# score_anzeige_register.net
KiCad netlist of a schematic drawn in EAGLE
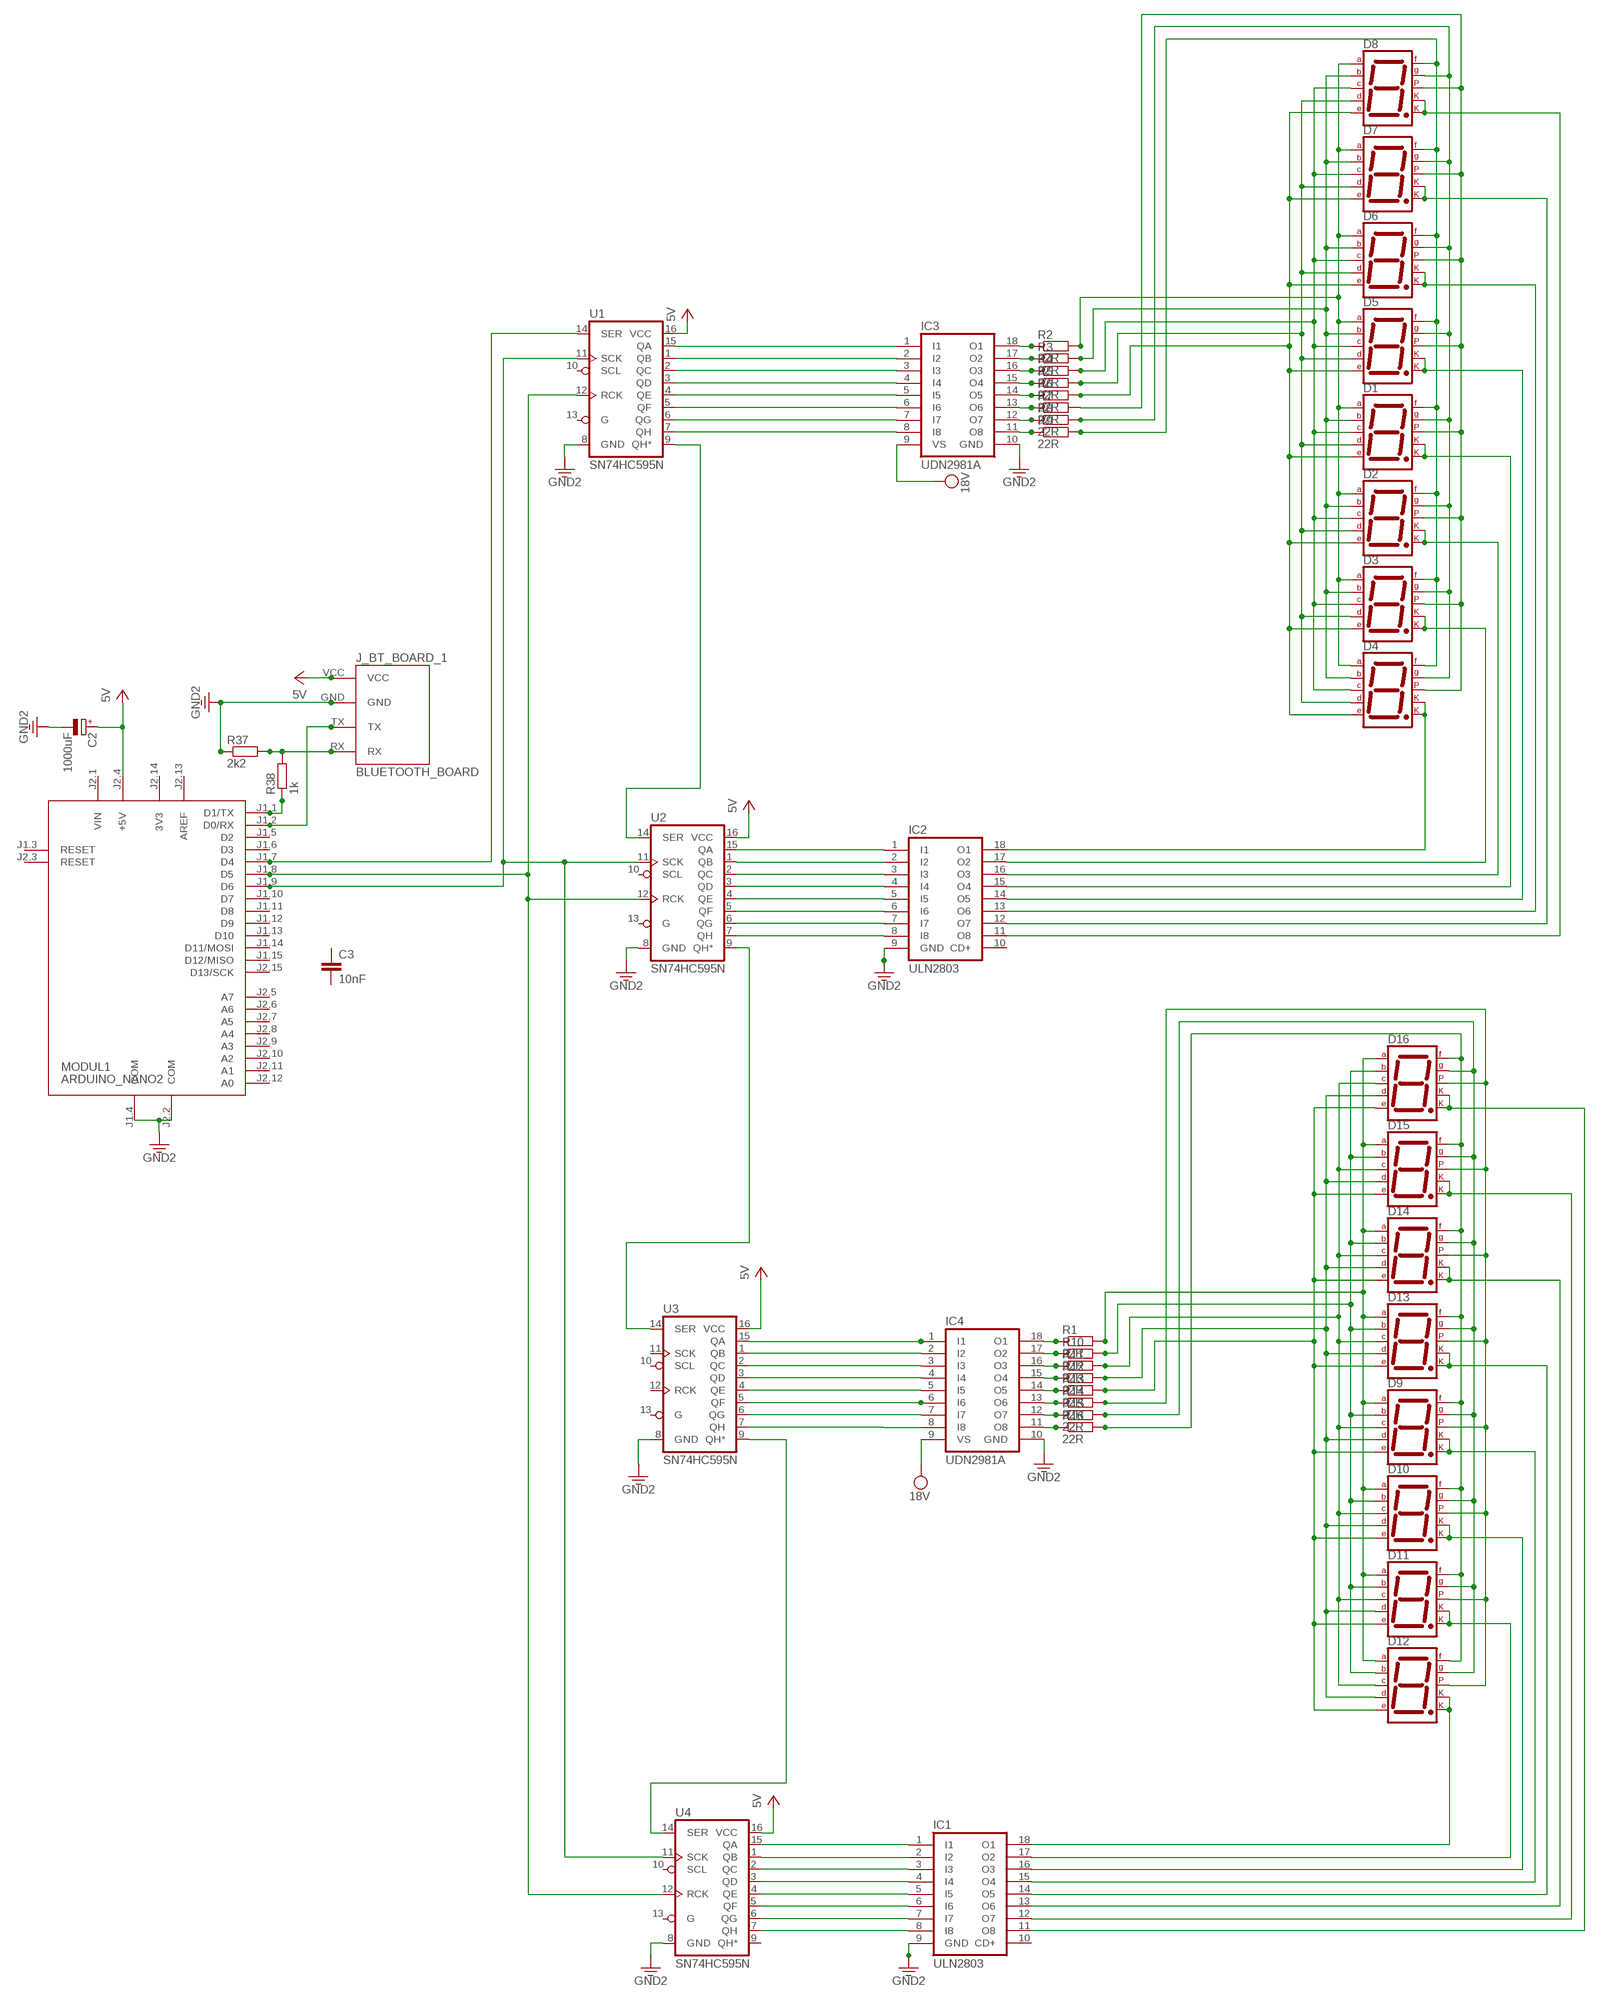
[diagram p0: schematic, sheet 1]

(export (version "E")
  (design (tool "Eeschema 10.0.6"))
  (components
    (comp (ref "C2")
      (value "1000uF")
      (footprint "eagle-import:E5-10,5")
      (libsource (lib "eagle-import") (part "CPOL-EUE5-10.5"))
    )
    (comp (ref "C3")
      (value "10nF")
      (footprint "eagle-import:C025-025X050")
      (libsource (lib "eagle-import") (part "C-EU025-025X050"))
    )
    (comp (ref "D1")
      (value "7SEG-MCK")
      (footprint "eagle-import:7SEG-7")
      (libsource (lib "eagle-import") (part "7SEG-MCK"))
    )
    (comp (ref "D2")
      (value "7SEG-MCK")
      (footprint "eagle-import:7SEG-7")
      (libsource (lib "eagle-import") (part "7SEG-MCK"))
    )
    (comp (ref "D3")
      (value "7SEG-MCK")
      (footprint "eagle-import:7SEG-7")
      (libsource (lib "eagle-import") (part "7SEG-MCK"))
    )
    (comp (ref "D4")
      (value "7SEG-MCK")
      (footprint "eagle-import:7SEG-7")
      (libsource (lib "eagle-import") (part "7SEG-MCK"))
    )
    (comp (ref "D5")
      (value "7SEG-MCK")
      (footprint "eagle-import:7SEG-7")
      (libsource (lib "eagle-import") (part "7SEG-MCK"))
    )
    (comp (ref "D6")
      (value "7SEG-MCK")
      (footprint "eagle-import:7SEG-7")
      (libsource (lib "eagle-import") (part "7SEG-MCK"))
    )
    (comp (ref "D7")
      (value "7SEG-MCK")
      (footprint "eagle-import:7SEG-7")
      (libsource (lib "eagle-import") (part "7SEG-MCK"))
    )
    (comp (ref "D8")
      (value "7SEG-MCK")
      (footprint "eagle-import:7SEG-7")
      (libsource (lib "eagle-import") (part "7SEG-MCK"))
    )
    (comp (ref "D9")
      (value "7SEG-MCK")
      (footprint "eagle-import:7SEG-7")
      (libsource (lib "eagle-import") (part "7SEG-MCK"))
    )
    (comp (ref "D10")
      (value "7SEG-MCK")
      (footprint "eagle-import:7SEG-7")
      (libsource (lib "eagle-import") (part "7SEG-MCK"))
    )
    (comp (ref "D11")
      (value "7SEG-MCK")
      (footprint "eagle-import:7SEG-7")
      (libsource (lib "eagle-import") (part "7SEG-MCK"))
    )
    (comp (ref "D12")
      (value "7SEG-MCK")
      (footprint "eagle-import:7SEG-7")
      (libsource (lib "eagle-import") (part "7SEG-MCK"))
    )
    (comp (ref "D13")
      (value "7SEG-MCK")
      (footprint "eagle-import:7SEG-7")
      (libsource (lib "eagle-import") (part "7SEG-MCK"))
    )
    (comp (ref "D14")
      (value "7SEG-MCK")
      (footprint "eagle-import:7SEG-7")
      (libsource (lib "eagle-import") (part "7SEG-MCK"))
    )
    (comp (ref "D15")
      (value "7SEG-MCK")
      (footprint "eagle-import:7SEG-7")
      (libsource (lib "eagle-import") (part "7SEG-MCK"))
    )
    (comp (ref "D16")
      (value "7SEG-MCK")
      (footprint "eagle-import:7SEG-7")
      (libsource (lib "eagle-import") (part "7SEG-MCK"))
    )
    (comp (ref "IC1")
      (value "ULN2803")
      (footprint "eagle-import:DIL18")
      (libsource (lib "eagle-import") (part "ULN2803A"))
    )
    (comp (ref "IC2")
      (value "ULN2803")
      (footprint "eagle-import:DIL18")
      (libsource (lib "eagle-import") (part "ULN2803A"))
    )
    (comp (ref "IC3")
      (value "UDN2981A")
      (footprint "eagle-import:DIL18")
      (libsource (lib "eagle-import") (part "UDN298A1"))
    )
    (comp (ref "IC4")
      (value "UDN2981A")
      (footprint "eagle-import:DIL18")
      (libsource (lib "eagle-import") (part "UDN298A1"))
    )
    (comp (ref "J_BT_BOARD_1")
      (value "BLUETOOTH_BOARD")
      (footprint "eagle-import:BT_BOARD_FOOTPRINT")
      (libsource (lib "eagle-import") (part "BLUETOOTH_BOARD"))
    )
    (comp (ref "MODUL1")
      (value "ARDUINO_NANO2")
      (footprint "eagle-import:ARDUINO_NANO2")
      (libsource (lib "eagle-import") (part "ARDUINO_NANO2"))
    )
    (comp (ref "R1")
      (value "22R")
      (footprint "eagle-import:0204_7")
      (libsource (lib "eagle-import") (part "R-EU_0204/7"))
    )
    (comp (ref "R2")
      (value "22R")
      (footprint "eagle-import:0204_7")
      (libsource (lib "eagle-import") (part "R-EU_0204/7"))
    )
    (comp (ref "R3")
      (value "22R")
      (footprint "eagle-import:0204_7")
      (libsource (lib "eagle-import") (part "R-EU_0204/7"))
    )
    (comp (ref "R4")
      (value "22R")
      (footprint "eagle-import:0204_7")
      (libsource (lib "eagle-import") (part "R-EU_0204/7"))
    )
    (comp (ref "R5")
      (value "22R")
      (footprint "eagle-import:0204_7")
      (libsource (lib "eagle-import") (part "R-EU_0204/7"))
    )
    (comp (ref "R6")
      (value "22R")
      (footprint "eagle-import:0204_7")
      (libsource (lib "eagle-import") (part "R-EU_0204/7"))
    )
    (comp (ref "R7")
      (value "22R")
      (footprint "eagle-import:0204_7")
      (libsource (lib "eagle-import") (part "R-EU_0204/7"))
    )
    (comp (ref "R8")
      (value "22R")
      (footprint "eagle-import:0204_7")
      (libsource (lib "eagle-import") (part "R-EU_0204/7"))
    )
    (comp (ref "R9")
      (value "22R")
      (footprint "eagle-import:0204_7")
      (libsource (lib "eagle-import") (part "R-EU_0204/7"))
    )
    (comp (ref "R10")
      (value "22R")
      (footprint "eagle-import:0204_7")
      (libsource (lib "eagle-import") (part "R-EU_0204/7"))
    )
    (comp (ref "R11")
      (value "22R")
      (footprint "eagle-import:0204_7")
      (libsource (lib "eagle-import") (part "R-EU_0204/7"))
    )
    (comp (ref "R12")
      (value "22R")
      (footprint "eagle-import:0204_7")
      (libsource (lib "eagle-import") (part "R-EU_0204/7"))
    )
    (comp (ref "R13")
      (value "22R")
      (footprint "eagle-import:0204_7")
      (libsource (lib "eagle-import") (part "R-EU_0204/7"))
    )
    (comp (ref "R14")
      (value "22R")
      (footprint "eagle-import:0204_7")
      (libsource (lib "eagle-import") (part "R-EU_0204/7"))
    )
    (comp (ref "R15")
      (value "22R")
      (footprint "eagle-import:0204_7")
      (libsource (lib "eagle-import") (part "R-EU_0204/7"))
    )
    (comp (ref "R16")
      (value "22R")
      (footprint "eagle-import:0204_7")
      (libsource (lib "eagle-import") (part "R-EU_0204/7"))
    )
    (comp (ref "R37")
      (value "2k2")
      (footprint "eagle-import:0204_7")
      (libsource (lib "eagle-import") (part "R-EU_0204/7"))
    )
    (comp (ref "R38")
      (value "1k")
      (footprint "eagle-import:0204_7")
      (libsource (lib "eagle-import") (part "R-EU_0204/7"))
    )
    (comp (ref "U1")
      (value "SN74HC595N")
      (footprint "eagle-import:DIP16")
      (libsource (lib "eagle-import") (part "74595NHC"))
    )
    (comp (ref "U2")
      (value "SN74HC595N")
      (footprint "eagle-import:DIP16")
      (libsource (lib "eagle-import") (part "74595NHC"))
    )
    (comp (ref "U3")
      (value "SN74HC595N")
      (footprint "eagle-import:DIP16")
      (libsource (lib "eagle-import") (part "74595NHC"))
    )
    (comp (ref "U4")
      (value "SN74HC595N")
      (footprint "eagle-import:DIP16")
      (libsource (lib "eagle-import") (part "74595NHC"))
    )
  )
  (nets
    (net (code "1") (name "/3V3") (class "Default")
      (node (ref "MODUL1") (pin "J2.14") (pinfunction "3V3_J2.14") (pintype "power_in"))
    )
    (net (code "2") (name "/AREF") (class "Default")
      (node (ref "MODUL1") (pin "J2.13") (pinfunction "AREF_J2.13") (pintype "power_in"))
    )
    (net (code "3") (name "/VIN") (class "Default")
      (node (ref "MODUL1") (pin "J2.1") (pinfunction "VIN_J2.1") (pintype "power_in"))
    )
    (net (code "4") (name "18V") (class "Default")
      (node (ref "C2") (pin "+") (pinfunction "+_+") (pintype "passive"))
      (node (ref "IC3") (pin "9") (pinfunction "VS_9") (pintype "passive"))
      (node (ref "IC4") (pin "9") (pinfunction "VS_9") (pintype "passive"))
      (node (ref "J_BT_BOARD_1") (pin "VCC") (pinfunction "VCC_VCC") (pintype "bidirectional"))
      (node (ref "MODUL1") (pin "J2.4") (pinfunction "+5V_J2.4") (pintype "power_in"))
      (node (ref "U1") (pin "16") (pinfunction "VCC_16") (pintype "power_in"))
      (node (ref "U2") (pin "16") (pinfunction "VCC_16") (pintype "power_in"))
      (node (ref "U3") (pin "16") (pinfunction "VCC_16") (pintype "power_in"))
      (node (ref "U4") (pin "16") (pinfunction "VCC_16") (pintype "power_in"))
    )
    (net (code "5") (name "GND2") (class "Default")
      (node (ref "C2") (pin "-") (pinfunction "-_-") (pintype "passive"))
      (node (ref "IC1") (pin "9") (pinfunction "GND_9") (pintype "power_in"))
      (node (ref "IC2") (pin "9") (pinfunction "GND_9") (pintype "power_in"))
      (node (ref "IC3") (pin "10") (pinfunction "GND_10") (pintype "power_in"))
      (node (ref "IC4") (pin "10") (pinfunction "GND_10") (pintype "power_in"))
      (node (ref "J_BT_BOARD_1") (pin "GND") (pinfunction "GND_GND") (pintype "bidirectional"))
      (node (ref "MODUL1") (pin "J1.4") (pinfunction "COM_J1.4") (pintype "power_in"))
      (node (ref "MODUL1") (pin "J2.2") (pinfunction "COM_J2.2") (pintype "power_in"))
      (node (ref "R37") (pin "1") (pinfunction "1_1") (pintype "passive"))
      (node (ref "U1") (pin "8") (pinfunction "GND_8") (pintype "power_in"))
      (node (ref "U2") (pin "8") (pinfunction "GND_8") (pintype "power_in"))
      (node (ref "U3") (pin "8") (pinfunction "GND_8") (pintype "power_in"))
      (node (ref "U4") (pin "8") (pinfunction "GND_8") (pintype "power_in"))
    )
    (net (code "6") (name "Net-(D1-A)") (class "Default")
      (node (ref "D1") (pin "10") (pinfunction "A_10") (pintype "passive"))
      (node (ref "D2") (pin "10") (pinfunction "A_10") (pintype "passive"))
      (node (ref "D3") (pin "10") (pinfunction "A_10") (pintype "passive"))
      (node (ref "D4") (pin "10") (pinfunction "A_10") (pintype "passive"))
      (node (ref "D5") (pin "10") (pinfunction "A_10") (pintype "passive"))
      (node (ref "D6") (pin "10") (pinfunction "A_10") (pintype "passive"))
      (node (ref "D7") (pin "10") (pinfunction "A_10") (pintype "passive"))
      (node (ref "D8") (pin "10") (pinfunction "A_10") (pintype "passive"))
      (node (ref "R2") (pin "2") (pinfunction "2_2") (pintype "passive"))
    )
    (net (code "7") (name "Net-(D1-B)") (class "Default")
      (node (ref "D1") (pin "9") (pinfunction "B_9") (pintype "passive"))
      (node (ref "D2") (pin "9") (pinfunction "B_9") (pintype "passive"))
      (node (ref "D3") (pin "9") (pinfunction "B_9") (pintype "passive"))
      (node (ref "D4") (pin "9") (pinfunction "B_9") (pintype "passive"))
      (node (ref "D5") (pin "9") (pinfunction "B_9") (pintype "passive"))
      (node (ref "D6") (pin "9") (pinfunction "B_9") (pintype "passive"))
      (node (ref "D7") (pin "9") (pinfunction "B_9") (pintype "passive"))
      (node (ref "D8") (pin "9") (pinfunction "B_9") (pintype "passive"))
      (node (ref "R3") (pin "2") (pinfunction "2_2") (pintype "passive"))
    )
    (net (code "8") (name "Net-(D1-C)") (class "Default")
      (node (ref "D1") (pin "8") (pinfunction "C_8") (pintype "passive"))
      (node (ref "D2") (pin "8") (pinfunction "C_8") (pintype "passive"))
      (node (ref "D3") (pin "8") (pinfunction "C_8") (pintype "passive"))
      (node (ref "D4") (pin "8") (pinfunction "C_8") (pintype "passive"))
      (node (ref "D5") (pin "8") (pinfunction "C_8") (pintype "passive"))
      (node (ref "D6") (pin "8") (pinfunction "C_8") (pintype "passive"))
      (node (ref "D7") (pin "8") (pinfunction "C_8") (pintype "passive"))
      (node (ref "D8") (pin "8") (pinfunction "C_8") (pintype "passive"))
      (node (ref "R4") (pin "2") (pinfunction "2_2") (pintype "passive"))
    )
    (net (code "9") (name "Net-(D1-CK1)") (class "Default")
      (node (ref "D1") (pin "1") (pinfunction "CK1_1") (pintype "passive"))
      (node (ref "D1") (pin "6") (pinfunction "CK2_6") (pintype "passive"))
      (node (ref "IC2") (pin "15") (pinfunction "O4_15") (pintype "open_collector"))
    )
    (net (code "10") (name "Net-(D1-D)") (class "Default")
      (node (ref "D1") (pin "5") (pinfunction "D_5") (pintype "passive"))
      (node (ref "D2") (pin "5") (pinfunction "D_5") (pintype "passive"))
      (node (ref "D3") (pin "5") (pinfunction "D_5") (pintype "passive"))
      (node (ref "D4") (pin "5") (pinfunction "D_5") (pintype "passive"))
      (node (ref "D5") (pin "5") (pinfunction "D_5") (pintype "passive"))
      (node (ref "D6") (pin "5") (pinfunction "D_5") (pintype "passive"))
      (node (ref "D7") (pin "5") (pinfunction "D_5") (pintype "passive"))
      (node (ref "D8") (pin "5") (pinfunction "D_5") (pintype "passive"))
      (node (ref "R5") (pin "2") (pinfunction "2_2") (pintype "passive"))
    )
    (net (code "11") (name "Net-(D1-DP)") (class "Default")
      (node (ref "D1") (pin "7") (pinfunction "DP_7") (pintype "passive"))
      (node (ref "D2") (pin "7") (pinfunction "DP_7") (pintype "passive"))
      (node (ref "D3") (pin "7") (pinfunction "DP_7") (pintype "passive"))
      (node (ref "D4") (pin "7") (pinfunction "DP_7") (pintype "passive"))
      (node (ref "D5") (pin "7") (pinfunction "DP_7") (pintype "passive"))
      (node (ref "D6") (pin "7") (pinfunction "DP_7") (pintype "passive"))
      (node (ref "D7") (pin "7") (pinfunction "DP_7") (pintype "passive"))
      (node (ref "D8") (pin "7") (pinfunction "DP_7") (pintype "passive"))
      (node (ref "R7") (pin "2") (pinfunction "2_2") (pintype "passive"))
    )
    (net (code "12") (name "Net-(D1-E)") (class "Default")
      (node (ref "D1") (pin "4") (pinfunction "E_4") (pintype "passive"))
      (node (ref "D2") (pin "4") (pinfunction "E_4") (pintype "passive"))
      (node (ref "D3") (pin "4") (pinfunction "E_4") (pintype "passive"))
      (node (ref "D4") (pin "4") (pinfunction "E_4") (pintype "passive"))
      (node (ref "D5") (pin "4") (pinfunction "E_4") (pintype "passive"))
      (node (ref "D6") (pin "4") (pinfunction "E_4") (pintype "passive"))
      (node (ref "D7") (pin "4") (pinfunction "E_4") (pintype "passive"))
      (node (ref "D8") (pin "4") (pinfunction "E_4") (pintype "passive"))
      (node (ref "R6") (pin "2") (pinfunction "2_2") (pintype "passive"))
    )
    (net (code "13") (name "Net-(D1-F)") (class "Default")
      (node (ref "D1") (pin "2") (pinfunction "F_2") (pintype "passive"))
      (node (ref "D2") (pin "2") (pinfunction "F_2") (pintype "passive"))
      (node (ref "D3") (pin "2") (pinfunction "F_2") (pintype "passive"))
      (node (ref "D4") (pin "2") (pinfunction "F_2") (pintype "passive"))
      (node (ref "D5") (pin "2") (pinfunction "F_2") (pintype "passive"))
      (node (ref "D6") (pin "2") (pinfunction "F_2") (pintype "passive"))
      (node (ref "D7") (pin "2") (pinfunction "F_2") (pintype "passive"))
      (node (ref "D8") (pin "2") (pinfunction "F_2") (pintype "passive"))
      (node (ref "R9") (pin "2") (pinfunction "2_2") (pintype "passive"))
    )
    (net (code "14") (name "Net-(D1-G)") (class "Default")
      (node (ref "D1") (pin "3") (pinfunction "G_3") (pintype "passive"))
      (node (ref "D2") (pin "3") (pinfunction "G_3") (pintype "passive"))
      (node (ref "D3") (pin "3") (pinfunction "G_3") (pintype "passive"))
      (node (ref "D4") (pin "3") (pinfunction "G_3") (pintype "passive"))
      (node (ref "D5") (pin "3") (pinfunction "G_3") (pintype "passive"))
      (node (ref "D6") (pin "3") (pinfunction "G_3") (pintype "passive"))
      (node (ref "D7") (pin "3") (pinfunction "G_3") (pintype "passive"))
      (node (ref "D8") (pin "3") (pinfunction "G_3") (pintype "passive"))
      (node (ref "R8") (pin "2") (pinfunction "2_2") (pintype "passive"))
    )
    (net (code "15") (name "Net-(D2-CK1)") (class "Default")
      (node (ref "D2") (pin "1") (pinfunction "CK1_1") (pintype "passive"))
      (node (ref "D2") (pin "6") (pinfunction "CK2_6") (pintype "passive"))
      (node (ref "IC2") (pin "16") (pinfunction "O3_16") (pintype "open_collector"))
    )
    (net (code "16") (name "Net-(D3-CK1)") (class "Default")
      (node (ref "D3") (pin "1") (pinfunction "CK1_1") (pintype "passive"))
      (node (ref "D3") (pin "6") (pinfunction "CK2_6") (pintype "passive"))
      (node (ref "IC2") (pin "17") (pinfunction "O2_17") (pintype "open_collector"))
    )
    (net (code "17") (name "Net-(D4-CK1)") (class "Default")
      (node (ref "D4") (pin "1") (pinfunction "CK1_1") (pintype "passive"))
      (node (ref "D4") (pin "6") (pinfunction "CK2_6") (pintype "passive"))
      (node (ref "IC2") (pin "18") (pinfunction "O1_18") (pintype "open_collector"))
    )
    (net (code "18") (name "Net-(D5-CK1)") (class "Default")
      (node (ref "D5") (pin "1") (pinfunction "CK1_1") (pintype "passive"))
      (node (ref "D5") (pin "6") (pinfunction "CK2_6") (pintype "passive"))
      (node (ref "IC2") (pin "14") (pinfunction "O5_14") (pintype "open_collector"))
    )
    (net (code "19") (name "Net-(D6-CK1)") (class "Default")
      (node (ref "D6") (pin "1") (pinfunction "CK1_1") (pintype "passive"))
      (node (ref "D6") (pin "6") (pinfunction "CK2_6") (pintype "passive"))
      (node (ref "IC2") (pin "13") (pinfunction "O6_13") (pintype "open_collector"))
    )
    (net (code "20") (name "Net-(D7-CK1)") (class "Default")
      (node (ref "D7") (pin "1") (pinfunction "CK1_1") (pintype "passive"))
      (node (ref "D7") (pin "6") (pinfunction "CK2_6") (pintype "passive"))
      (node (ref "IC2") (pin "12") (pinfunction "O7_12") (pintype "open_collector"))
    )
    (net (code "21") (name "Net-(D8-CK1)") (class "Default")
      (node (ref "D8") (pin "1") (pinfunction "CK1_1") (pintype "passive"))
      (node (ref "D8") (pin "6") (pinfunction "CK2_6") (pintype "passive"))
      (node (ref "IC2") (pin "11") (pinfunction "O8_11") (pintype "open_collector"))
    )
    (net (code "22") (name "Net-(D9-CK1)") (class "Default")
      (node (ref "D9") (pin "1") (pinfunction "CK1_1") (pintype "passive"))
      (node (ref "D9") (pin "6") (pinfunction "CK2_6") (pintype "passive"))
      (node (ref "IC1") (pin "15") (pinfunction "O4_15") (pintype "open_collector"))
    )
    (net (code "23") (name "Net-(D10-A)") (class "Default")
      (node (ref "D10") (pin "10") (pinfunction "A_10") (pintype "passive"))
      (node (ref "D11") (pin "10") (pinfunction "A_10") (pintype "passive"))
      (node (ref "D12") (pin "10") (pinfunction "A_10") (pintype "passive"))
      (node (ref "D13") (pin "10") (pinfunction "A_10") (pintype "passive"))
      (node (ref "D14") (pin "10") (pinfunction "A_10") (pintype "passive"))
      (node (ref "D15") (pin "10") (pinfunction "A_10") (pintype "passive"))
      (node (ref "D16") (pin "10") (pinfunction "A_10") (pintype "passive"))
      (node (ref "D9") (pin "10") (pinfunction "A_10") (pintype "passive"))
      (node (ref "R1") (pin "2") (pinfunction "2_2") (pintype "passive"))
    )
    (net (code "24") (name "Net-(D10-B)") (class "Default")
      (node (ref "D10") (pin "9") (pinfunction "B_9") (pintype "passive"))
      (node (ref "D11") (pin "9") (pinfunction "B_9") (pintype "passive"))
      (node (ref "D12") (pin "9") (pinfunction "B_9") (pintype "passive"))
      (node (ref "D13") (pin "9") (pinfunction "B_9") (pintype "passive"))
      (node (ref "D14") (pin "9") (pinfunction "B_9") (pintype "passive"))
      (node (ref "D15") (pin "9") (pinfunction "B_9") (pintype "passive"))
      (node (ref "D16") (pin "9") (pinfunction "B_9") (pintype "passive"))
      (node (ref "D9") (pin "9") (pinfunction "B_9") (pintype "passive"))
      (node (ref "R10") (pin "2") (pinfunction "2_2") (pintype "passive"))
    )
    (net (code "25") (name "Net-(D10-C)") (class "Default")
      (node (ref "D10") (pin "8") (pinfunction "C_8") (pintype "passive"))
      (node (ref "D11") (pin "8") (pinfunction "C_8") (pintype "passive"))
      (node (ref "D12") (pin "8") (pinfunction "C_8") (pintype "passive"))
      (node (ref "D13") (pin "8") (pinfunction "C_8") (pintype "passive"))
      (node (ref "D14") (pin "8") (pinfunction "C_8") (pintype "passive"))
      (node (ref "D15") (pin "8") (pinfunction "C_8") (pintype "passive"))
      (node (ref "D16") (pin "8") (pinfunction "C_8") (pintype "passive"))
      (node (ref "D9") (pin "8") (pinfunction "C_8") (pintype "passive"))
      (node (ref "R11") (pin "2") (pinfunction "2_2") (pintype "passive"))
    )
    (net (code "26") (name "Net-(D10-CK1)") (class "Default")
      (node (ref "D10") (pin "1") (pinfunction "CK1_1") (pintype "passive"))
      (node (ref "D10") (pin "6") (pinfunction "CK2_6") (pintype "passive"))
      (node (ref "IC1") (pin "16") (pinfunction "O3_16") (pintype "open_collector"))
    )
    (net (code "27") (name "Net-(D10-D)") (class "Default")
      (node (ref "D10") (pin "5") (pinfunction "D_5") (pintype "passive"))
      (node (ref "D11") (pin "5") (pinfunction "D_5") (pintype "passive"))
      (node (ref "D12") (pin "5") (pinfunction "D_5") (pintype "passive"))
      (node (ref "D13") (pin "5") (pinfunction "D_5") (pintype "passive"))
      (node (ref "D14") (pin "5") (pinfunction "D_5") (pintype "passive"))
      (node (ref "D15") (pin "5") (pinfunction "D_5") (pintype "passive"))
      (node (ref "D16") (pin "5") (pinfunction "D_5") (pintype "passive"))
      (node (ref "D9") (pin "5") (pinfunction "D_5") (pintype "passive"))
      (node (ref "R12") (pin "2") (pinfunction "2_2") (pintype "passive"))
    )
    (net (code "28") (name "Net-(D10-DP)") (class "Default")
      (node (ref "D10") (pin "7") (pinfunction "DP_7") (pintype "passive"))
      (node (ref "D11") (pin "7") (pinfunction "DP_7") (pintype "passive"))
      (node (ref "D12") (pin "7") (pinfunction "DP_7") (pintype "passive"))
      (node (ref "D13") (pin "7") (pinfunction "DP_7") (pintype "passive"))
      (node (ref "D14") (pin "7") (pinfunction "DP_7") (pintype "passive"))
      (node (ref "D15") (pin "7") (pinfunction "DP_7") (pintype "passive"))
      (node (ref "D16") (pin "7") (pinfunction "DP_7") (pintype "passive"))
      (node (ref "D9") (pin "7") (pinfunction "DP_7") (pintype "passive"))
      (node (ref "R14") (pin "2") (pinfunction "2_2") (pintype "passive"))
    )
    (net (code "29") (name "Net-(D10-E)") (class "Default")
      (node (ref "D10") (pin "4") (pinfunction "E_4") (pintype "passive"))
      (node (ref "D11") (pin "4") (pinfunction "E_4") (pintype "passive"))
      (node (ref "D12") (pin "4") (pinfunction "E_4") (pintype "passive"))
      (node (ref "D13") (pin "4") (pinfunction "E_4") (pintype "passive"))
      (node (ref "D14") (pin "4") (pinfunction "E_4") (pintype "passive"))
      (node (ref "D15") (pin "4") (pinfunction "E_4") (pintype "passive"))
      (node (ref "D16") (pin "4") (pinfunction "E_4") (pintype "passive"))
      (node (ref "D9") (pin "4") (pinfunction "E_4") (pintype "passive"))
      (node (ref "R13") (pin "2") (pinfunction "2_2") (pintype "passive"))
    )
    (net (code "30") (name "Net-(D10-F)") (class "Default")
      (node (ref "D10") (pin "2") (pinfunction "F_2") (pintype "passive"))
      (node (ref "D11") (pin "2") (pinfunction "F_2") (pintype "passive"))
      (node (ref "D12") (pin "2") (pinfunction "F_2") (pintype "passive"))
      (node (ref "D13") (pin "2") (pinfunction "F_2") (pintype "passive"))
      (node (ref "D14") (pin "2") (pinfunction "F_2") (pintype "passive"))
      (node (ref "D15") (pin "2") (pinfunction "F_2") (pintype "passive"))
      (node (ref "D16") (pin "2") (pinfunction "F_2") (pintype "passive"))
      (node (ref "D9") (pin "2") (pinfunction "F_2") (pintype "passive"))
      (node (ref "R16") (pin "2") (pinfunction "2_2") (pintype "passive"))
    )
    (net (code "31") (name "Net-(D10-G)") (class "Default")
      (node (ref "D10") (pin "3") (pinfunction "G_3") (pintype "passive"))
      (node (ref "D11") (pin "3") (pinfunction "G_3") (pintype "passive"))
      (node (ref "D12") (pin "3") (pinfunction "G_3") (pintype "passive"))
      (node (ref "D13") (pin "3") (pinfunction "G_3") (pintype "passive"))
      (node (ref "D14") (pin "3") (pinfunction "G_3") (pintype "passive"))
      (node (ref "D15") (pin "3") (pinfunction "G_3") (pintype "passive"))
      (node (ref "D16") (pin "3") (pinfunction "G_3") (pintype "passive"))
      (node (ref "D9") (pin "3") (pinfunction "G_3") (pintype "passive"))
      (node (ref "R15") (pin "2") (pinfunction "2_2") (pintype "passive"))
    )
    (net (code "32") (name "Net-(D11-CK1)") (class "Default")
      (node (ref "D11") (pin "1") (pinfunction "CK1_1") (pintype "passive"))
      (node (ref "D11") (pin "6") (pinfunction "CK2_6") (pintype "passive"))
      (node (ref "IC1") (pin "17") (pinfunction "O2_17") (pintype "open_collector"))
    )
    (net (code "33") (name "Net-(D12-CK1)") (class "Default")
      (node (ref "D12") (pin "1") (pinfunction "CK1_1") (pintype "passive"))
      (node (ref "D12") (pin "6") (pinfunction "CK2_6") (pintype "passive"))
      (node (ref "IC1") (pin "18") (pinfunction "O1_18") (pintype "open_collector"))
    )
    (net (code "34") (name "Net-(D13-CK1)") (class "Default")
      (node (ref "D13") (pin "1") (pinfunction "CK1_1") (pintype "passive"))
      (node (ref "D13") (pin "6") (pinfunction "CK2_6") (pintype "passive"))
      (node (ref "IC1") (pin "14") (pinfunction "O5_14") (pintype "open_collector"))
    )
    (net (code "35") (name "Net-(D14-CK1)") (class "Default")
      (node (ref "D14") (pin "1") (pinfunction "CK1_1") (pintype "passive"))
      (node (ref "D14") (pin "6") (pinfunction "CK2_6") (pintype "passive"))
      (node (ref "IC1") (pin "13") (pinfunction "O6_13") (pintype "open_collector"))
    )
    (net (code "36") (name "Net-(D15-CK1)") (class "Default")
      (node (ref "D15") (pin "1") (pinfunction "CK1_1") (pintype "passive"))
      (node (ref "D15") (pin "6") (pinfunction "CK2_6") (pintype "passive"))
      (node (ref "IC1") (pin "12") (pinfunction "O7_12") (pintype "open_collector"))
    )
    (net (code "37") (name "Net-(D16-CK1)") (class "Default")
      (node (ref "D16") (pin "1") (pinfunction "CK1_1") (pintype "passive"))
      (node (ref "D16") (pin "6") (pinfunction "CK2_6") (pintype "passive"))
      (node (ref "IC1") (pin "11") (pinfunction "O8_11") (pintype "open_collector"))
    )
    (net (code "38") (name "Net-(IC1-I1)") (class "Default")
      (node (ref "IC1") (pin "1") (pinfunction "I1_1") (pintype "input"))
      (node (ref "U4") (pin "15") (pinfunction "QA_15") (pintype "tri_state"))
    )
    (net (code "39") (name "Net-(IC1-I2)") (class "Default")
      (node (ref "IC1") (pin "2") (pinfunction "I2_2") (pintype "input"))
      (node (ref "U4") (pin "1") (pinfunction "QB_1") (pintype "tri_state"))
    )
    (net (code "40") (name "Net-(IC1-I3)") (class "Default")
      (node (ref "IC1") (pin "3") (pinfunction "I3_3") (pintype "input"))
      (node (ref "U4") (pin "2") (pinfunction "QC_2") (pintype "tri_state"))
    )
    (net (code "41") (name "Net-(IC1-I4)") (class "Default")
      (node (ref "IC1") (pin "4") (pinfunction "I4_4") (pintype "input"))
      (node (ref "U4") (pin "3") (pinfunction "QD_3") (pintype "tri_state"))
    )
    (net (code "42") (name "Net-(IC1-I5)") (class "Default")
      (node (ref "IC1") (pin "5") (pinfunction "I5_5") (pintype "input"))
      (node (ref "U4") (pin "4") (pinfunction "QE_4") (pintype "tri_state"))
    )
    (net (code "43") (name "Net-(IC1-I6)") (class "Default")
      (node (ref "IC1") (pin "6") (pinfunction "I6_6") (pintype "input"))
      (node (ref "U4") (pin "5") (pinfunction "QF_5") (pintype "tri_state"))
    )
    (net (code "44") (name "Net-(IC1-I7)") (class "Default")
      (node (ref "IC1") (pin "7") (pinfunction "I7_7") (pintype "input"))
      (node (ref "U4") (pin "6") (pinfunction "QG_6") (pintype "tri_state"))
    )
    (net (code "45") (name "Net-(IC1-I8)") (class "Default")
      (node (ref "IC1") (pin "8") (pinfunction "I8_8") (pintype "input"))
      (node (ref "U4") (pin "7") (pinfunction "QH_7") (pintype "tri_state"))
    )
    (net (code "46") (name "Net-(IC2-I1)") (class "Default")
      (node (ref "IC2") (pin "1") (pinfunction "I1_1") (pintype "input"))
      (node (ref "U2") (pin "15") (pinfunction "QA_15") (pintype "tri_state"))
    )
    (net (code "47") (name "Net-(IC2-I2)") (class "Default")
      (node (ref "IC2") (pin "2") (pinfunction "I2_2") (pintype "input"))
      (node (ref "U2") (pin "1") (pinfunction "QB_1") (pintype "tri_state"))
    )
    (net (code "48") (name "Net-(IC2-I3)") (class "Default")
      (node (ref "IC2") (pin "3") (pinfunction "I3_3") (pintype "input"))
      (node (ref "U2") (pin "2") (pinfunction "QC_2") (pintype "tri_state"))
    )
    (net (code "49") (name "Net-(IC2-I4)") (class "Default")
      (node (ref "IC2") (pin "4") (pinfunction "I4_4") (pintype "input"))
      (node (ref "U2") (pin "3") (pinfunction "QD_3") (pintype "tri_state"))
    )
    (net (code "50") (name "Net-(IC2-I5)") (class "Default")
      (node (ref "IC2") (pin "5") (pinfunction "I5_5") (pintype "input"))
      (node (ref "U2") (pin "4") (pinfunction "QE_4") (pintype "tri_state"))
    )
    (net (code "51") (name "Net-(IC2-I6)") (class "Default")
      (node (ref "IC2") (pin "6") (pinfunction "I6_6") (pintype "input"))
      (node (ref "U2") (pin "5") (pinfunction "QF_5") (pintype "tri_state"))
    )
    (net (code "52") (name "Net-(IC2-I7)") (class "Default")
      (node (ref "IC2") (pin "7") (pinfunction "I7_7") (pintype "input"))
      (node (ref "U2") (pin "6") (pinfunction "QG_6") (pintype "tri_state"))
    )
    (net (code "53") (name "Net-(IC2-I8)") (class "Default")
      (node (ref "IC2") (pin "8") (pinfunction "I8_8") (pintype "input"))
      (node (ref "U2") (pin "7") (pinfunction "QH_7") (pintype "tri_state"))
    )
    (net (code "54") (name "Net-(IC3-I1)") (class "Default")
      (node (ref "IC3") (pin "1") (pinfunction "I1_1") (pintype "input"))
      (node (ref "U1") (pin "15") (pinfunction "QA_15") (pintype "tri_state"))
    )
    (net (code "55") (name "Net-(IC3-I2)") (class "Default")
      (node (ref "IC3") (pin "2") (pinfunction "I2_2") (pintype "input"))
      (node (ref "U1") (pin "1") (pinfunction "QB_1") (pintype "tri_state"))
    )
    (net (code "56") (name "Net-(IC3-I3)") (class "Default")
      (node (ref "IC3") (pin "3") (pinfunction "I3_3") (pintype "input"))
      (node (ref "U1") (pin "2") (pinfunction "QC_2") (pintype "tri_state"))
    )
    (net (code "57") (name "Net-(IC3-I4)") (class "Default")
      (node (ref "IC3") (pin "4") (pinfunction "I4_4") (pintype "input"))
      (node (ref "U1") (pin "3") (pinfunction "QD_3") (pintype "tri_state"))
    )
    (net (code "58") (name "Net-(IC3-I5)") (class "Default")
      (node (ref "IC3") (pin "5") (pinfunction "I5_5") (pintype "input"))
      (node (ref "U1") (pin "4") (pinfunction "QE_4") (pintype "tri_state"))
    )
    (net (code "59") (name "Net-(IC3-I6)") (class "Default")
      (node (ref "IC3") (pin "6") (pinfunction "I6_6") (pintype "input"))
      (node (ref "U1") (pin "5") (pinfunction "QF_5") (pintype "tri_state"))
    )
    (net (code "60") (name "Net-(IC3-I7)") (class "Default")
      (node (ref "IC3") (pin "7") (pinfunction "I7_7") (pintype "input"))
      (node (ref "U1") (pin "6") (pinfunction "QG_6") (pintype "tri_state"))
    )
    (net (code "61") (name "Net-(IC3-I8)") (class "Default")
      (node (ref "IC3") (pin "8") (pinfunction "I8_8") (pintype "input"))
      (node (ref "U1") (pin "7") (pinfunction "QH_7") (pintype "tri_state"))
    )
    (net (code "62") (name "Net-(IC3-O1)") (class "Default")
      (node (ref "IC3") (pin "18") (pinfunction "O1_18") (pintype "open_collector"))
      (node (ref "R2") (pin "1") (pinfunction "1_1") (pintype "passive"))
    )
    (net (code "63") (name "Net-(IC3-O2)") (class "Default")
      (node (ref "IC3") (pin "17") (pinfunction "O2_17") (pintype "open_collector"))
      (node (ref "R3") (pin "1") (pinfunction "1_1") (pintype "passive"))
    )
    (net (code "64") (name "Net-(IC3-O3)") (class "Default")
      (node (ref "IC3") (pin "16") (pinfunction "O3_16") (pintype "open_collector"))
      (node (ref "R4") (pin "1") (pinfunction "1_1") (pintype "passive"))
    )
    (net (code "65") (name "Net-(IC3-O4)") (class "Default")
      (node (ref "IC3") (pin "15") (pinfunction "O4_15") (pintype "open_collector"))
      (node (ref "R5") (pin "1") (pinfunction "1_1") (pintype "passive"))
    )
    (net (code "66") (name "Net-(IC3-O5)") (class "Default")
      (node (ref "IC3") (pin "14") (pinfunction "O5_14") (pintype "open_collector"))
      (node (ref "R6") (pin "1") (pinfunction "1_1") (pintype "passive"))
    )
    (net (code "67") (name "Net-(IC3-O6)") (class "Default")
      (node (ref "IC3") (pin "13") (pinfunction "O6_13") (pintype "open_collector"))
      (node (ref "R7") (pin "1") (pinfunction "1_1") (pintype "passive"))
    )
    (net (code "68") (name "Net-(IC3-O7)") (class "Default")
      (node (ref "IC3") (pin "12") (pinfunction "O7_12") (pintype "open_collector"))
      (node (ref "R8") (pin "1") (pinfunction "1_1") (pintype "passive"))
    )
    (net (code "69") (name "Net-(IC3-O8)") (class "Default")
      (node (ref "IC3") (pin "11") (pinfunction "O8_11") (pintype "open_collector"))
      (node (ref "R9") (pin "1") (pinfunction "1_1") (pintype "passive"))
    )
    (net (code "70") (name "Net-(IC4-I1)") (class "Default")
      (node (ref "IC4") (pin "1") (pinfunction "I1_1") (pintype "input"))
      (node (ref "U3") (pin "15") (pinfunction "QA_15") (pintype "tri_state"))
    )
    (net (code "71") (name "Net-(IC4-I2)") (class "Default")
      (node (ref "IC4") (pin "2") (pinfunction "I2_2") (pintype "input"))
      (node (ref "U3") (pin "1") (pinfunction "QB_1") (pintype "tri_state"))
    )
    (net (code "72") (name "Net-(IC4-I3)") (class "Default")
      (node (ref "IC4") (pin "3") (pinfunction "I3_3") (pintype "input"))
      (node (ref "U3") (pin "2") (pinfunction "QC_2") (pintype "tri_state"))
    )
    (net (code "73") (name "Net-(IC4-I4)") (class "Default")
      (node (ref "IC4") (pin "4") (pinfunction "I4_4") (pintype "input"))
      (node (ref "U3") (pin "3") (pinfunction "QD_3") (pintype "tri_state"))
    )
    (net (code "74") (name "Net-(IC4-I5)") (class "Default")
      (node (ref "IC4") (pin "5") (pinfunction "I5_5") (pintype "input"))
      (node (ref "U3") (pin "4") (pinfunction "QE_4") (pintype "tri_state"))
    )
    (net (code "75") (name "Net-(IC4-I6)") (class "Default")
      (node (ref "IC4") (pin "6") (pinfunction "I6_6") (pintype "input"))
      (node (ref "U3") (pin "5") (pinfunction "QF_5") (pintype "tri_state"))
    )
    (net (code "76") (name "Net-(IC4-I7)") (class "Default")
      (node (ref "IC4") (pin "7") (pinfunction "I7_7") (pintype "input"))
      (node (ref "U3") (pin "6") (pinfunction "QG_6") (pintype "tri_state"))
    )
    (net (code "77") (name "Net-(IC4-I8)") (class "Default")
      (node (ref "IC4") (pin "8") (pinfunction "I8_8") (pintype "input"))
      (node (ref "U3") (pin "7") (pinfunction "QH_7") (pintype "tri_state"))
    )
    (net (code "78") (name "Net-(IC4-O1)") (class "Default")
      (node (ref "IC4") (pin "18") (pinfunction "O1_18") (pintype "open_collector"))
      (node (ref "R1") (pin "1") (pinfunction "1_1") (pintype "passive"))
    )
    (net (code "79") (name "Net-(IC4-O2)") (class "Default")
      (node (ref "IC4") (pin "17") (pinfunction "O2_17") (pintype "open_collector"))
      (node (ref "R10") (pin "1") (pinfunction "1_1") (pintype "passive"))
    )
    (net (code "80") (name "Net-(IC4-O3)") (class "Default")
      (node (ref "IC4") (pin "16") (pinfunction "O3_16") (pintype "open_collector"))
      (node (ref "R11") (pin "1") (pinfunction "1_1") (pintype "passive"))
    )
    (net (code "81") (name "Net-(IC4-O4)") (class "Default")
      (node (ref "IC4") (pin "15") (pinfunction "O4_15") (pintype "open_collector"))
      (node (ref "R12") (pin "1") (pinfunction "1_1") (pintype "passive"))
    )
    (net (code "82") (name "Net-(IC4-O5)") (class "Default")
      (node (ref "IC4") (pin "14") (pinfunction "O5_14") (pintype "open_collector"))
      (node (ref "R13") (pin "1") (pinfunction "1_1") (pintype "passive"))
    )
    (net (code "83") (name "Net-(IC4-O6)") (class "Default")
      (node (ref "IC4") (pin "13") (pinfunction "O6_13") (pintype "open_collector"))
      (node (ref "R14") (pin "1") (pinfunction "1_1") (pintype "passive"))
    )
    (net (code "84") (name "Net-(IC4-O7)") (class "Default")
      (node (ref "IC4") (pin "12") (pinfunction "O7_12") (pintype "open_collector"))
      (node (ref "R15") (pin "1") (pinfunction "1_1") (pintype "passive"))
    )
    (net (code "85") (name "Net-(IC4-O8)") (class "Default")
      (node (ref "IC4") (pin "11") (pinfunction "O8_11") (pintype "open_collector"))
      (node (ref "R16") (pin "1") (pinfunction "1_1") (pintype "passive"))
    )
    (net (code "86") (name "Net-(J_BT_BOARD_1-PadRX)") (class "Default")
      (node (ref "J_BT_BOARD_1") (pin "RX") (pinfunction "RX_RX") (pintype "bidirectional"))
      (node (ref "R37") (pin "2") (pinfunction "2_2") (pintype "passive"))
      (node (ref "R38") (pin "2") (pinfunction "2_2") (pintype "passive"))
    )
    (net (code "87") (name "Net-(MODUL1-D0{slash}RX)") (class "Default")
      (node (ref "J_BT_BOARD_1") (pin "TX") (pinfunction "TX_TX") (pintype "bidirectional"))
      (node (ref "MODUL1") (pin "J1.2") (pinfunction "D0/RX_J1.2") (pintype "bidirectional"))
    )
    (net (code "88") (name "Net-(MODUL1-D1{slash}TX)") (class "Default")
      (node (ref "MODUL1") (pin "J1.1") (pinfunction "D1/TX_J1.1") (pintype "bidirectional"))
      (node (ref "R38") (pin "1") (pinfunction "1_1") (pintype "passive"))
    )
    (net (code "89") (name "Net-(MODUL1-D4)") (class "Default")
      (node (ref "MODUL1") (pin "J1.7") (pinfunction "D4_J1.7") (pintype "bidirectional"))
      (node (ref "U1") (pin "14") (pinfunction "SER_14") (pintype "input"))
    )
    (net (code "90") (name "Net-(MODUL1-D5)") (class "Default")
      (node (ref "MODUL1") (pin "J1.8") (pinfunction "D5_J1.8") (pintype "bidirectional"))
      (node (ref "U1") (pin "12") (pinfunction "RCK_12") (pintype "input"))
      (node (ref "U2") (pin "12") (pinfunction "RCK_12") (pintype "input"))
      (node (ref "U4") (pin "12") (pinfunction "RCK_12") (pintype "input"))
    )
    (net (code "91") (name "Net-(MODUL1-D6)") (class "Default")
      (node (ref "MODUL1") (pin "J1.9") (pinfunction "D6_J1.9") (pintype "bidirectional"))
      (node (ref "U1") (pin "11") (pinfunction "SCK_11") (pintype "input"))
      (node (ref "U2") (pin "11") (pinfunction "SCK_11") (pintype "input"))
      (node (ref "U4") (pin "11") (pinfunction "SCK_11") (pintype "input"))
    )
    (net (code "92") (name "Net-(U1-QH*)") (class "Default")
      (node (ref "U1") (pin "9") (pinfunction "QH*_9") (pintype "tri_state"))
      (node (ref "U2") (pin "14") (pinfunction "SER_14") (pintype "input"))
    )
    (net (code "93") (name "Net-(U2-QH*)") (class "Default")
      (node (ref "U2") (pin "9") (pinfunction "QH*_9") (pintype "tri_state"))
      (node (ref "U3") (pin "14") (pinfunction "SER_14") (pintype "input"))
    )
    (net (code "94") (name "Net-(U3-QH*)") (class "Default")
      (node (ref "U3") (pin "9") (pinfunction "QH*_9") (pintype "tri_state"))
      (node (ref "U4") (pin "14") (pinfunction "SER_14") (pintype "input"))
    )
    (net (code "95") (name "unconnected-(C3-Pad1)") (class "Default")
      (node (ref "C3") (pin "1") (pinfunction "1_1") (pintype "passive"))
    )
    (net (code "96") (name "unconnected-(C3-Pad2)") (class "Default")
      (node (ref "C3") (pin "2") (pinfunction "2_2") (pintype "passive"))
    )
    (net (code "97") (name "unconnected-(IC1-CD+-Pad10)") (class "Default")
      (node (ref "IC1") (pin "10") (pinfunction "CD+_10") (pintype "passive"))
    )
    (net (code "98") (name "unconnected-(IC2-CD+-Pad10)") (class "Default")
      (node (ref "IC2") (pin "10") (pinfunction "CD+_10") (pintype "passive"))
    )
    (net (code "99") (name "unconnected-(MODUL1-A0-PadJ2.12)") (class "Default")
      (node (ref "MODUL1") (pin "J2.12") (pinfunction "A0_J2.12") (pintype "bidirectional"))
    )
    (net (code "100") (name "unconnected-(MODUL1-A1-PadJ2.11)") (class "Default")
      (node (ref "MODUL1") (pin "J2.11") (pinfunction "A1_J2.11") (pintype "bidirectional"))
    )
    (net (code "101") (name "unconnected-(MODUL1-A2-PadJ2.10)") (class "Default")
      (node (ref "MODUL1") (pin "J2.10") (pinfunction "A2_J2.10") (pintype "bidirectional"))
    )
    (net (code "102") (name "unconnected-(MODUL1-A3-PadJ2.9)") (class "Default")
      (node (ref "MODUL1") (pin "J2.9") (pinfunction "A3_J2.9") (pintype "bidirectional"))
    )
    (net (code "103") (name "unconnected-(MODUL1-A4-PadJ2.8)") (class "Default")
      (node (ref "MODUL1") (pin "J2.8") (pinfunction "A4_J2.8") (pintype "bidirectional"))
    )
    (net (code "104") (name "unconnected-(MODUL1-A5-PadJ2.7)") (class "Default")
      (node (ref "MODUL1") (pin "J2.7") (pinfunction "A5_J2.7") (pintype "bidirectional"))
    )
    (net (code "105") (name "unconnected-(MODUL1-A6-PadJ2.6)") (class "Default")
      (node (ref "MODUL1") (pin "J2.6") (pinfunction "A6_J2.6") (pintype "bidirectional"))
    )
    (net (code "106") (name "unconnected-(MODUL1-A7-PadJ2.5)") (class "Default")
      (node (ref "MODUL1") (pin "J2.5") (pinfunction "A7_J2.5") (pintype "bidirectional"))
    )
    (net (code "107") (name "unconnected-(MODUL1-D2-PadJ1.5)") (class "Default")
      (node (ref "MODUL1") (pin "J1.5") (pinfunction "D2_J1.5") (pintype "bidirectional"))
    )
    (net (code "108") (name "unconnected-(MODUL1-D3-PadJ1.6)") (class "Default")
      (node (ref "MODUL1") (pin "J1.6") (pinfunction "D3_J1.6") (pintype "bidirectional"))
    )
    (net (code "109") (name "unconnected-(MODUL1-D7-PadJ1.10)") (class "Default")
      (node (ref "MODUL1") (pin "J1.10") (pinfunction "D7_J1.10") (pintype "bidirectional"))
    )
    (net (code "110") (name "unconnected-(MODUL1-D8-PadJ1.11)") (class "Default")
      (node (ref "MODUL1") (pin "J1.11") (pinfunction "D8_J1.11") (pintype "bidirectional"))
    )
    (net (code "111") (name "unconnected-(MODUL1-D9-PadJ1.12)") (class "Default")
      (node (ref "MODUL1") (pin "J1.12") (pinfunction "D9_J1.12") (pintype "bidirectional"))
    )
    (net (code "112") (name "unconnected-(MODUL1-D10-PadJ1.13)") (class "Default")
      (node (ref "MODUL1") (pin "J1.13") (pinfunction "D10_J1.13") (pintype "bidirectional"))
    )
    (net (code "113") (name "unconnected-(MODUL1-D11{slash}MOSI-PadJ1.14)") (class "Default")
      (node (ref "MODUL1") (pin "J1.14") (pinfunction "D11/MOSI_J1.14") (pintype "bidirectional"))
    )
    (net (code "114") (name "unconnected-(MODUL1-D12{slash}MISO-PadJ1.15)") (class "Default")
      (node (ref "MODUL1") (pin "J1.15") (pinfunction "D12/MISO_J1.15") (pintype "bidirectional"))
    )
    (net (code "115") (name "unconnected-(MODUL1-D13{slash}SCK-PadJ2.15)") (class "Default")
      (node (ref "MODUL1") (pin "J2.15") (pinfunction "D13/SCK_J2.15") (pintype "bidirectional"))
    )
    (net (code "116") (name "unconnected-(MODUL1-RESET-PadJ1.3)") (class "Default")
      (node (ref "MODUL1") (pin "J1.3") (pinfunction "RESET_J1.3") (pintype "bidirectional"))
    )
    (net (code "117") (name "unconnected-(MODUL1-RESET-PadJ2.3)") (class "Default")
      (node (ref "MODUL1") (pin "J2.3") (pinfunction "RESET_J2.3") (pintype "bidirectional"))
    )
    (net (code "118") (name "unconnected-(U1-G-Pad13)") (class "Default")
      (node (ref "U1") (pin "13") (pinfunction "G_13") (pintype "input"))
    )
    (net (code "119") (name "unconnected-(U1-SCL-Pad10)") (class "Default")
      (node (ref "U1") (pin "10") (pinfunction "SCL_10") (pintype "input"))
    )
    (net (code "120") (name "unconnected-(U2-G-Pad13)") (class "Default")
      (node (ref "U2") (pin "13") (pinfunction "G_13") (pintype "input"))
    )
    (net (code "121") (name "unconnected-(U2-SCL-Pad10)") (class "Default")
      (node (ref "U2") (pin "10") (pinfunction "SCL_10") (pintype "input"))
    )
    (net (code "122") (name "unconnected-(U3-G-Pad13)") (class "Default")
      (node (ref "U3") (pin "13") (pinfunction "G_13") (pintype "input"))
    )
    (net (code "123") (name "unconnected-(U3-RCK-Pad12)") (class "Default")
      (node (ref "U3") (pin "12") (pinfunction "RCK_12") (pintype "input"))
    )
    (net (code "124") (name "unconnected-(U3-SCK-Pad11)") (class "Default")
      (node (ref "U3") (pin "11") (pinfunction "SCK_11") (pintype "input"))
    )
    (net (code "125") (name "unconnected-(U3-SCL-Pad10)") (class "Default")
      (node (ref "U3") (pin "10") (pinfunction "SCL_10") (pintype "input"))
    )
    (net (code "126") (name "unconnected-(U4-G-Pad13)") (class "Default")
      (node (ref "U4") (pin "13") (pinfunction "G_13") (pintype "input"))
    )
    (net (code "127") (name "unconnected-(U4-QH*-Pad9)") (class "Default")
      (node (ref "U4") (pin "9") (pinfunction "QH*_9") (pintype "tri_state"))
    )
    (net (code "128") (name "unconnected-(U4-SCL-Pad10)") (class "Default")
      (node (ref "U4") (pin "10") (pinfunction "SCL_10") (pintype "input"))
    )
  )
)
